# blink1mk3_micro1d.net
KiCad netlist of a schematic drawn in EAGLE
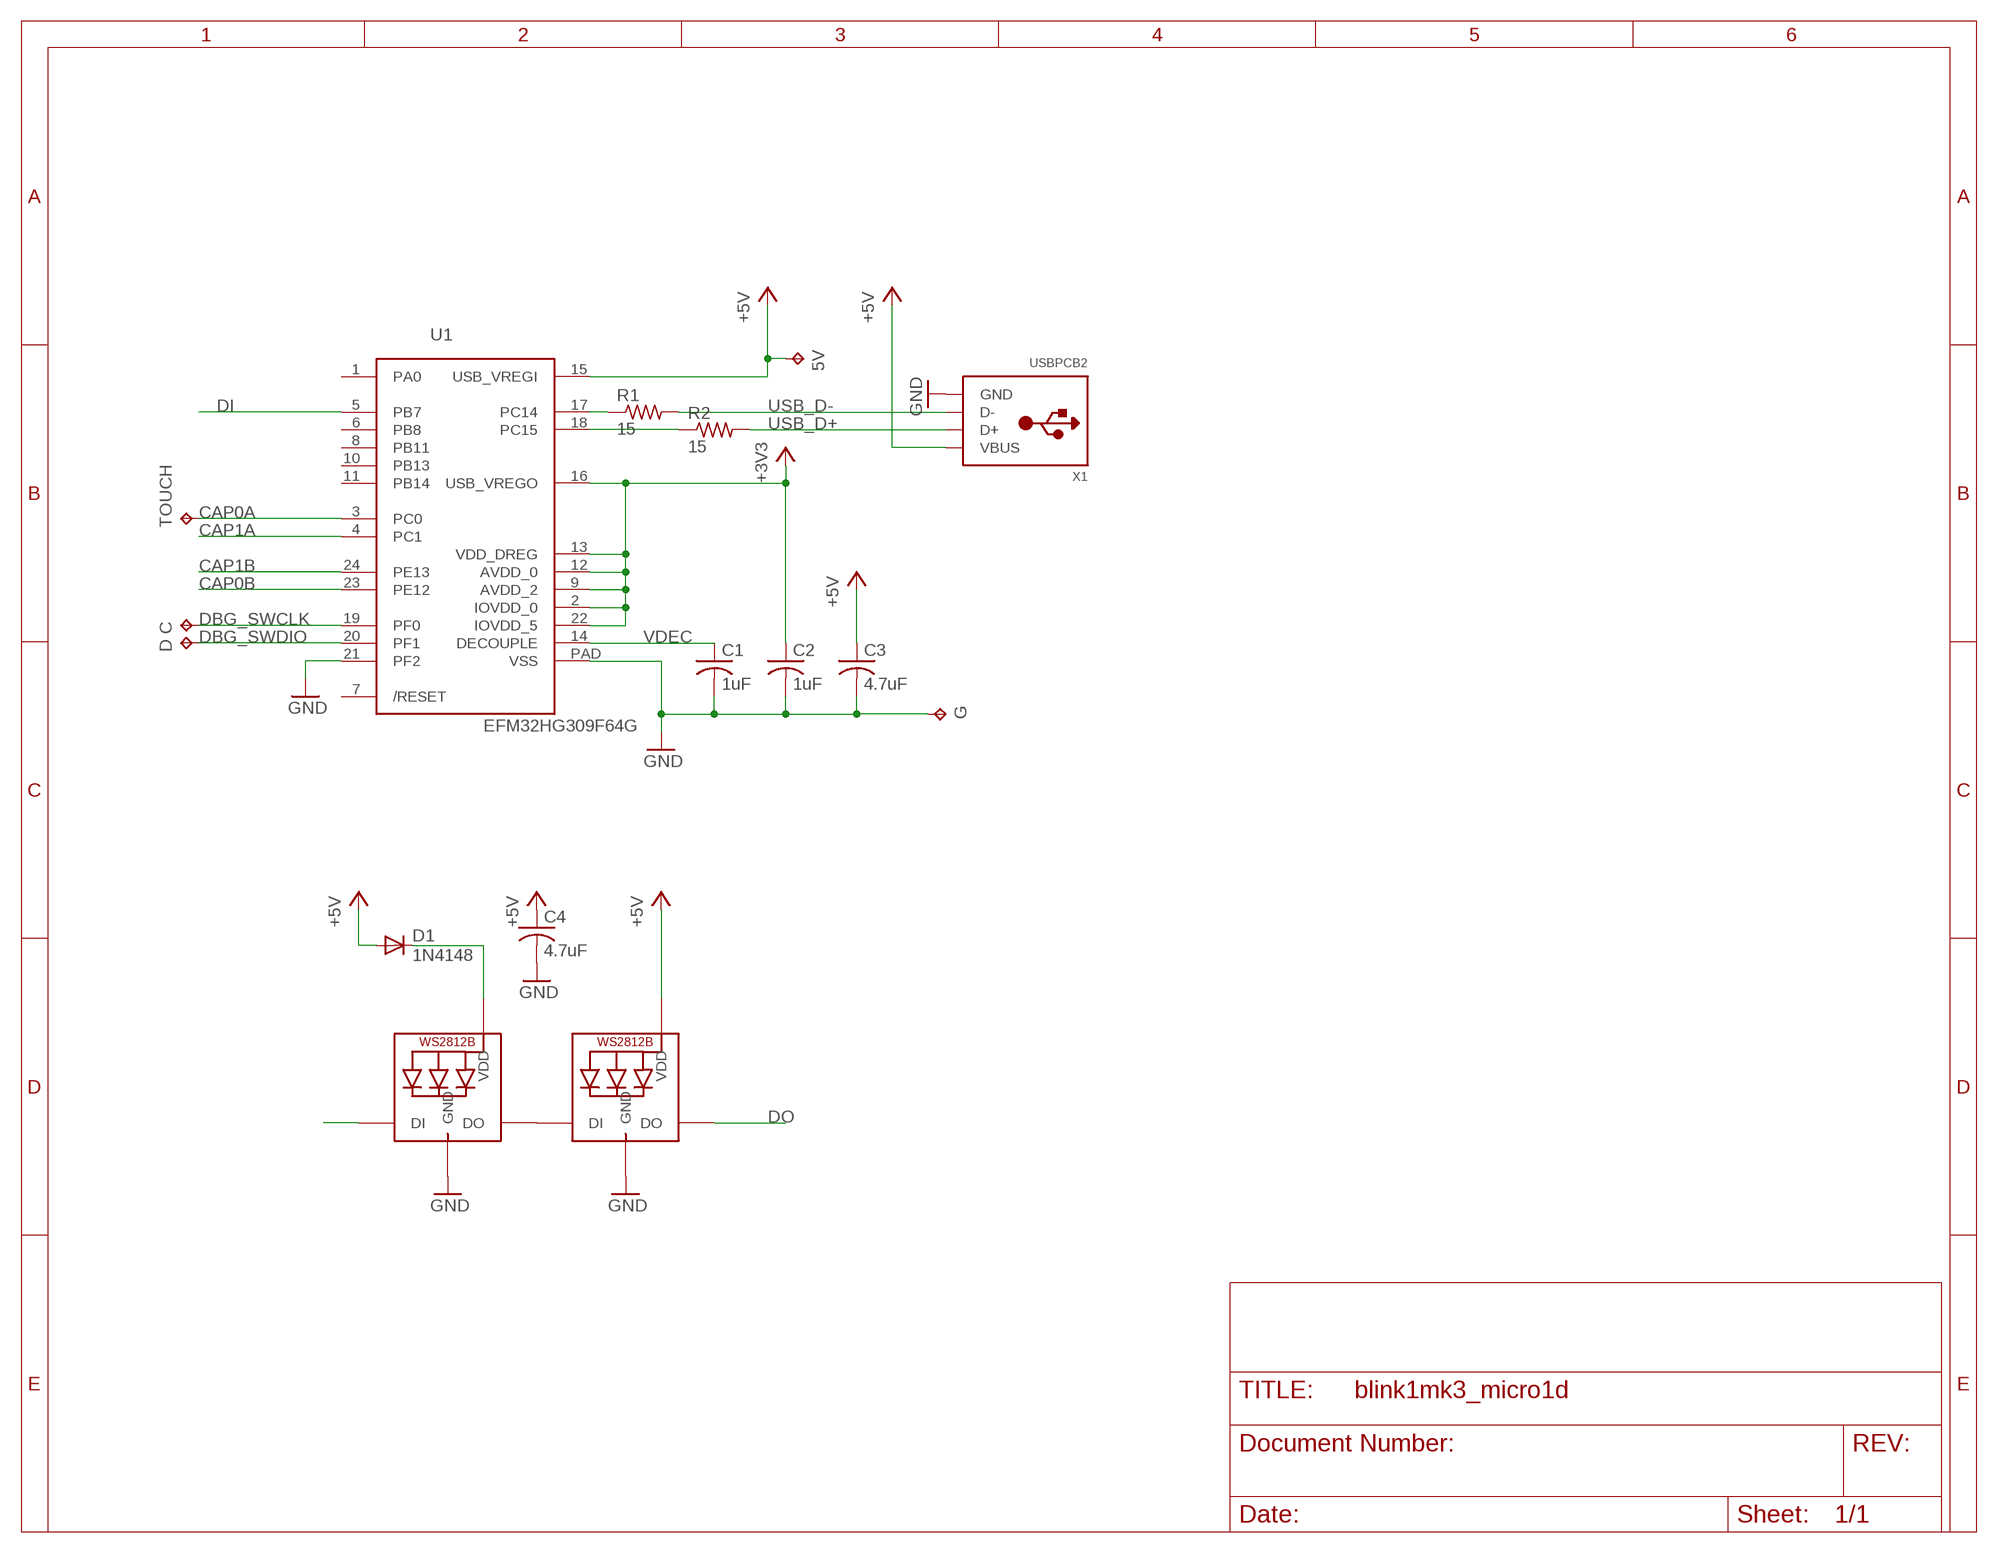
[diagram p0: schematic, sheet 1]

(export (version "E")
  (design (tool "Eeschema 10.0.6"))
  (components
    (comp (ref "5V")
      (value "TPTP10R")
      (footprint "eagle-import:TP10R")
      (libsource (lib "eagle-import") (part "TPTP10R"))
    )
    (comp (ref "C")
      (value "TPTP10R")
      (footprint "eagle-import:TP10R")
      (libsource (lib "eagle-import") (part "TPTP10R"))
    )
    (comp (ref "C1")
      (value "1uF")
      (footprint "eagle-import:C0402")
      (libsource (lib "eagle-import") (part "C-USC0402"))
    )
    (comp (ref "C2")
      (value "1uF")
      (footprint "eagle-import:C0402")
      (libsource (lib "eagle-import") (part "C-USC0402"))
    )
    (comp (ref "C3")
      (value "4.7uF")
      (footprint "eagle-import:C0402")
      (libsource (lib "eagle-import") (part "C-USC0402"))
    )
    (comp (ref "C4")
      (value "4.7uF")
      (footprint "eagle-import:C0402")
      (libsource (lib "eagle-import") (part "C-USC0402"))
    )
    (comp (ref "D")
      (value "TPTP10R")
      (footprint "eagle-import:TP10R")
      (libsource (lib "eagle-import") (part "TPTP10R"))
    )
    (comp (ref "D1")
      (value "1N4148")
      (footprint "eagle-import:SOD523")
      (libsource (lib "eagle-import") (part "DIODE-SOD523"))
    )
    (comp (ref "G")
      (value "TPTP10SQ")
      (footprint "eagle-import:TP10SQ")
      (libsource (lib "eagle-import") (part "TPTP10SQ"))
    )
    (comp (ref "LED1")
      (value "WS2812B4020SIDE")
      (footprint "eagle-import:SK6812-SIDE")
      (libsource (lib "eagle-import") (part "WS2812B4020SIDE"))
    )
    (comp (ref "LED2")
      (value "WS2812B4020SIDE")
      (footprint "eagle-import:SK6812-SIDE")
      (libsource (lib "eagle-import") (part "WS2812B4020SIDE"))
    )
    (comp (ref "R1")
      (value "15")
      (footprint "eagle-import:R0402")
      (libsource (lib "eagle-import") (part "R-US_R0402"))
    )
    (comp (ref "R2")
      (value "15")
      (footprint "eagle-import:R0402")
      (libsource (lib "eagle-import") (part "R-US_R0402"))
    )
    (comp (ref "TOUCH")
      (value "TPTP10R")
      (footprint "eagle-import:TP10R")
      (libsource (lib "eagle-import") (part "TPTP10R"))
    )
    (comp (ref "U1")
      (value "EFM32HG309F64G")
      (footprint "eagle-import:QFN24PAD")
      (libsource (lib "eagle-import") (part "EFM32HG309F64G"))
    )
    (comp (ref "X1")
      (value "USBPCB2")
      (footprint "eagle-import:USB-A-PCB-2")
      (libsource (lib "eagle-import") (part "USBPCB2"))
    )
  )
  (nets
    (net (code "1") (name "+3V3") (class "Default")
      (node (ref "C2") (pin "1") (pinfunction "1_1") (pintype "passive"))
      (node (ref "U1") (pin "12") (pinfunction "AVDD_0_12") (pintype "bidirectional"))
      (node (ref "U1") (pin "13") (pinfunction "VDD_DREG_13") (pintype "bidirectional"))
      (node (ref "U1") (pin "16") (pinfunction "USB_VREGO_16") (pintype "bidirectional"))
      (node (ref "U1") (pin "2") (pinfunction "IOVDD_0_2") (pintype "bidirectional"))
      (node (ref "U1") (pin "22") (pinfunction "IOVDD_5_22") (pintype "bidirectional"))
      (node (ref "U1") (pin "9") (pinfunction "AVDD_2_9") (pintype "bidirectional"))
    )
    (net (code "2") (name "+5V") (class "Default")
      (node (ref "5V") (pin "TP") (pinfunction "TP_TP") (pintype "input"))
      (node (ref "C3") (pin "1") (pinfunction "1_1") (pintype "passive"))
      (node (ref "C4") (pin "1") (pinfunction "1_1") (pintype "passive"))
      (node (ref "D1") (pin "A") (pinfunction "A_A") (pintype "passive"))
      (node (ref "LED2") (pin "1-VDD") (pinfunction "VDD_1-VDD") (pintype "power_in"))
      (node (ref "U1") (pin "15") (pinfunction "USB_VREGI_15") (pintype "bidirectional"))
      (node (ref "X1") (pin "5V") (pinfunction "VBUS_5V") (pintype "power_in"))
    )
    (net (code "3") (name "/CAP0A") (class "Default")
      (node (ref "TOUCH") (pin "TP") (pinfunction "TP_TP") (pintype "input"))
      (node (ref "U1") (pin "3") (pinfunction "PC0_3") (pintype "bidirectional"))
    )
    (net (code "4") (name "/CAP0B") (class "Default")
      (node (ref "U1") (pin "23") (pinfunction "PE12_23") (pintype "bidirectional"))
    )
    (net (code "5") (name "/CAP1A") (class "Default")
      (node (ref "U1") (pin "4") (pinfunction "PC1_4") (pintype "bidirectional"))
    )
    (net (code "6") (name "/CAP1B") (class "Default")
      (node (ref "U1") (pin "24") (pinfunction "PE13_24") (pintype "bidirectional"))
    )
    (net (code "7") (name "/DBG_SWCLK") (class "Default")
      (node (ref "C") (pin "TP") (pinfunction "TP_TP") (pintype "input"))
      (node (ref "U1") (pin "19") (pinfunction "PF0_19") (pintype "bidirectional"))
    )
    (net (code "8") (name "/DBG_SWDIO") (class "Default")
      (node (ref "D") (pin "TP") (pinfunction "TP_TP") (pintype "input"))
      (node (ref "U1") (pin "20") (pinfunction "PF1_20") (pintype "bidirectional"))
    )
    (net (code "9") (name "/DI") (class "Default")
      (node (ref "LED1") (pin "4-DIN") (pinfunction "DI_4-DIN") (pintype "input"))
      (node (ref "U1") (pin "5") (pinfunction "PB7_5") (pintype "bidirectional"))
    )
    (net (code "10") (name "/DO") (class "Default")
      (node (ref "LED2") (pin "2-DOUT") (pinfunction "DO_2-DOUT") (pintype "output"))
    )
    (net (code "11") (name "/USB_D+") (class "Default")
      (node (ref "R2") (pin "2") (pinfunction "2_2") (pintype "passive"))
      (node (ref "X1") (pin "USB_P") (pinfunction "D+_USB_P") (pintype "bidirectional"))
    )
    (net (code "12") (name "/USB_D-") (class "Default")
      (node (ref "R1") (pin "2") (pinfunction "2_2") (pintype "passive"))
      (node (ref "X1") (pin "USB_M") (pinfunction "D-_USB_M") (pintype "bidirectional"))
    )
    (net (code "13") (name "/VDEC") (class "Default")
      (node (ref "C1") (pin "1") (pinfunction "1_1") (pintype "passive"))
      (node (ref "U1") (pin "14") (pinfunction "DECOUPLE_14") (pintype "bidirectional"))
    )
    (net (code "14") (name "GND") (class "Default")
      (node (ref "C1") (pin "2") (pinfunction "2_2") (pintype "passive"))
      (node (ref "C2") (pin "2") (pinfunction "2_2") (pintype "passive"))
      (node (ref "C3") (pin "2") (pinfunction "2_2") (pintype "passive"))
      (node (ref "C4") (pin "2") (pinfunction "2_2") (pintype "passive"))
      (node (ref "G") (pin "TP") (pinfunction "TP_TP") (pintype "input"))
      (node (ref "LED1") (pin "3-GND") (pinfunction "GND_3-GND") (pintype "power_in"))
      (node (ref "LED2") (pin "3-GND") (pinfunction "GND_3-GND") (pintype "power_in"))
      (node (ref "U1") (pin "21") (pinfunction "PF2_21") (pintype "bidirectional"))
      (node (ref "U1") (pin "PAD") (pinfunction "VSS_PAD") (pintype "bidirectional"))
      (node (ref "X1") (pin "GND") (pinfunction "GND_GND") (pintype "power_in"))
    )
    (net (code "15") (name "Net-(LED1-DO)") (class "Default")
      (node (ref "LED1") (pin "2-DOUT") (pinfunction "DO_2-DOUT") (pintype "output"))
      (node (ref "LED2") (pin "4-DIN") (pinfunction "DI_4-DIN") (pintype "input"))
    )
    (net (code "16") (name "Net-(LED1-VDD)") (class "Default")
      (node (ref "D1") (pin "C") (pinfunction "C_C") (pintype "passive"))
      (node (ref "LED1") (pin "1-VDD") (pinfunction "VDD_1-VDD") (pintype "power_in"))
    )
    (net (code "17") (name "Net-(U1-PC14)") (class "Default")
      (node (ref "R1") (pin "1") (pinfunction "1_1") (pintype "passive"))
      (node (ref "U1") (pin "17") (pinfunction "PC14_17") (pintype "bidirectional"))
    )
    (net (code "18") (name "Net-(U1-PC15)") (class "Default")
      (node (ref "R2") (pin "1") (pinfunction "1_1") (pintype "passive"))
      (node (ref "U1") (pin "18") (pinfunction "PC15_18") (pintype "bidirectional"))
    )
    (net (code "19") (name "unconnected-(U1-PA0-Pad1)") (class "Default")
      (node (ref "U1") (pin "1") (pinfunction "PA0_1") (pintype "bidirectional"))
    )
    (net (code "20") (name "unconnected-(U1-PB8-Pad6)") (class "Default")
      (node (ref "U1") (pin "6") (pinfunction "PB8_6") (pintype "bidirectional"))
    )
    (net (code "21") (name "unconnected-(U1-PB11-Pad8)") (class "Default")
      (node (ref "U1") (pin "8") (pinfunction "PB11_8") (pintype "bidirectional"))
    )
    (net (code "22") (name "unconnected-(U1-PB13-Pad10)") (class "Default")
      (node (ref "U1") (pin "10") (pinfunction "PB13_10") (pintype "bidirectional"))
    )
    (net (code "23") (name "unconnected-(U1-PB14-Pad11)") (class "Default")
      (node (ref "U1") (pin "11") (pinfunction "PB14_11") (pintype "bidirectional"))
    )
    (net (code "24") (name "unconnected-(U1-{slash}RESET-Pad7)") (class "Default")
      (node (ref "U1") (pin "7") (pinfunction "/RESET_7") (pintype "bidirectional"))
    )
  )
)
